# XL4015.net
KiCad netlist of a schematic drawn in Altium Designer
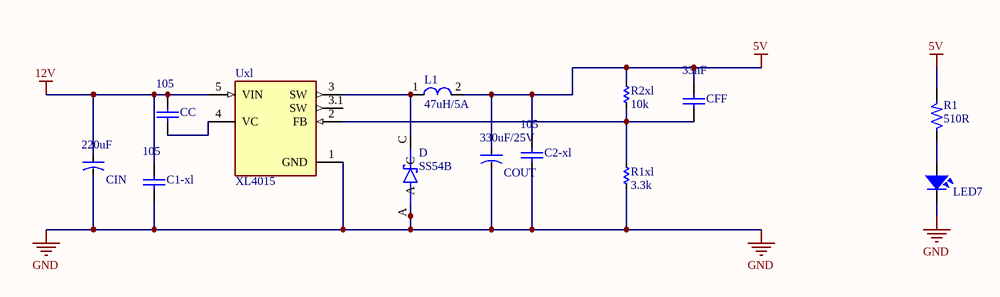
[diagram p0: XL4015.SchDoc]

(export (version "E")
  (design (tool "Eeschema 10.0.6"))
  (components
    (comp (ref "C1-xl")
      (value "105")
      (footprint "C0805")
      (description "Capacitor")
      (fields (field (name "PUBLISHER") "Altium Limited"))
      (libsource (lib "Schematic") (part "CapSMD"))
    )
    (comp (ref "C2-xl")
      (value "105")
      (footprint "C0805")
      (description "Capacitor")
      (fields (field (name "PUBLISHER") "Altium Limited"))
      (libsource (lib "Schematic") (part "CapSMD"))
    )
    (comp (ref "CC")
      (value "105")
      (footprint "C0805")
      (description "Capacitor")
      (fields (field (name "PUBLISHER") "Altium Limited"))
      (libsource (lib "Schematic") (part "CapSMD"))
    )
    (comp (ref "CFF")
      (value "33nF")
      (footprint "C0805")
      (description "Capacitor")
      (fields (field (name "PUBLISHER") "Altium Limited"))
      (libsource (lib "Schematic") (part "CapSMD"))
    )
    (comp (ref "CIN")
      (value "220uF")
      (footprint "CAP-ALU-SMD-6.3x7.7x2.2")
      (description "Polarized Capacitor (Axial)")
      (fields (field (name "PUBLISHER") "Altium Limited"))
      (libsource (lib "LIBRARYALT") (part "CN-ALU-SMD"))
    )
    (comp (ref "COUT")
      (value "330uF/25V")
      (footprint "CAP-ALU-SMD-F")
      (description "Polarized Capacitor (Axial)")
      (fields (field (name "PUBLISHER") "Altium Limited"))
      (libsource (lib "LIBRARYALT") (part "CN-ALU-SMD"))
    )
    (comp (ref "D")
      (value "SS54B")
      (footprint "DIOM4336X244N")
      (description "Diode Schottky 40V 5A Surface Mount SMBF")
      (fields (field (name "MF") "JCET"))
      (libsource (lib "SS54B") (part "SS54B"))
    )
    (comp (ref "L1")
      (value "47uH/5A")
      (footprint "L-DIP-M-18.5x8")
      (fields
        (field (name "PARTNO") "78477010")
        (field (name "MANUFACTURER") "Wurth Elektronik")
        (field (name "CREATED BY") "Baojun Chen")
      )
      (libsource (lib "My Library") (part "L-SMD-1"))
    )
    (comp (ref "LED7")
      (value "LED SMD")
      (footprint "SM-LED-0805-Blue")
      (libsource (lib "echipkool-com-library") (part "LED-SMD-0805"))
    )
    (comp (ref "R1")
      (value "510R")
      (footprint "SM-RES-0805")
      (description "Resistor 1/4W")
      (libsource (lib "syhaunguyen") (part "R"))
    )
    (comp (ref "R1xl")
      (value "3.3k")
      (footprint "RES-SMD-0805")
      (description "Resistor")
      (fields
        (field (name "MANUFACTURER") "Generic Components")
        (field (name "PUBLISHER") "Altium Hobart Technology Centre")
      )
      (libsource (lib "My Library") (part "Res-SMD"))
    )
    (comp (ref "R2xl")
      (value "10k")
      (footprint "RES-SMD-0805")
      (description "Resistor")
      (fields
        (field (name "MANUFACTURER") "Generic Components")
        (field (name "PUBLISHER") "Altium Hobart Technology Centre")
      )
      (libsource (lib "My Library") (part "Res-SMD"))
    )
    (comp (ref "Uxl")
      (value "XL4015")
      (footprint "CONV_XL4015")
      (description "5A 180KHz 36V Buck DC to DC Converter")
      (fields (field (name "MF") "XLSEMI"))
      (libsource (lib "XL4015") (part "XL4015"))
    )
  )
  (nets
    (net (code "1") (name "5V") (class "Default")
      (node (ref "C2-xl") (pin "2") (pinfunction "2_2") (pintype "passive"))
      (node (ref "CFF") (pin "2") (pinfunction "2_2") (pintype "passive"))
      (node (ref "COUT") (pin "1") (pinfunction "1_1") (pintype "passive"))
      (node (ref "L1") (pin "2") (pinfunction "2_2") (pintype "passive"))
      (node (ref "R1") (pin "2") (pinfunction "2_2") (pintype "passive"))
      (node (ref "R2xl") (pin "1") (pinfunction "1_1") (pintype "passive"))
    )
    (net (code "2") (name "12V") (class "Default")
      (node (ref "C1-xl") (pin "2") (pinfunction "2_2") (pintype "passive"))
      (node (ref "CC") (pin "2") (pinfunction "2_2") (pintype "passive"))
      (node (ref "CIN") (pin "1") (pinfunction "1_1") (pintype "passive"))
      (node (ref "Uxl") (pin "5") (pinfunction "VIN_5") (pintype "input"))
    )
    (net (code "3") (name "GND") (class "Default")
      (node (ref "C1-xl") (pin "1") (pinfunction "1_1") (pintype "passive"))
      (node (ref "C2-xl") (pin "1") (pinfunction "1_1") (pintype "passive"))
      (node (ref "CIN") (pin "2") (pinfunction "2_2") (pintype "passive"))
      (node (ref "COUT") (pin "2") (pinfunction "2_2") (pintype "passive"))
      (node (ref "D") (pin "A") (pinfunction "A_A") (pintype "passive"))
      (node (ref "LED7") (pin "2") (pinfunction "2_2") (pintype "passive"))
      (node (ref "R1xl") (pin "2") (pinfunction "2_2") (pintype "passive"))
      (node (ref "Uxl") (pin "1") (pinfunction "GND_1") (pintype "power_in"))
    )
    (net (code "4") (name "Net-(D-PadC)") (class "Default")
      (node (ref "D") (pin "C") (pinfunction "C_C") (pintype "passive"))
      (node (ref "L1") (pin "1") (pinfunction "1_1") (pintype "passive"))
      (node (ref "Uxl") (pin "3") (pinfunction "SW_3") (pintype "output"))
    )
    (net (code "5") (name "Net-(LED7-Pad1)") (class "Default")
      (node (ref "LED7") (pin "1") (pinfunction "1_1") (pintype "passive"))
      (node (ref "R1") (pin "1") (pinfunction "1_1") (pintype "passive"))
    )
    (net (code "6") (name "Net-(Uxl-FB)") (class "Default")
      (node (ref "CFF") (pin "1") (pinfunction "1_1") (pintype "passive"))
      (node (ref "R1xl") (pin "1") (pinfunction "1_1") (pintype "passive"))
      (node (ref "R2xl") (pin "2") (pinfunction "2_2") (pintype "passive"))
      (node (ref "Uxl") (pin "2") (pinfunction "FB_2") (pintype "input"))
    )
    (net (code "7") (name "Net-(Uxl-VC)") (class "Default")
      (node (ref "CC") (pin "1") (pinfunction "1_1") (pintype "passive"))
      (node (ref "Uxl") (pin "4") (pinfunction "VC_4") (pintype "passive"))
    )
    (net (code "8") (name "unconnected-(Uxl-SW-Pad3.1)") (class "Default")
      (node (ref "Uxl") (pin "3.1") (pinfunction "SW_3.1") (pintype "output"))
    )
  )
)
